# B115X.net
KiCad netlist of a schematic drawn in EAGLE
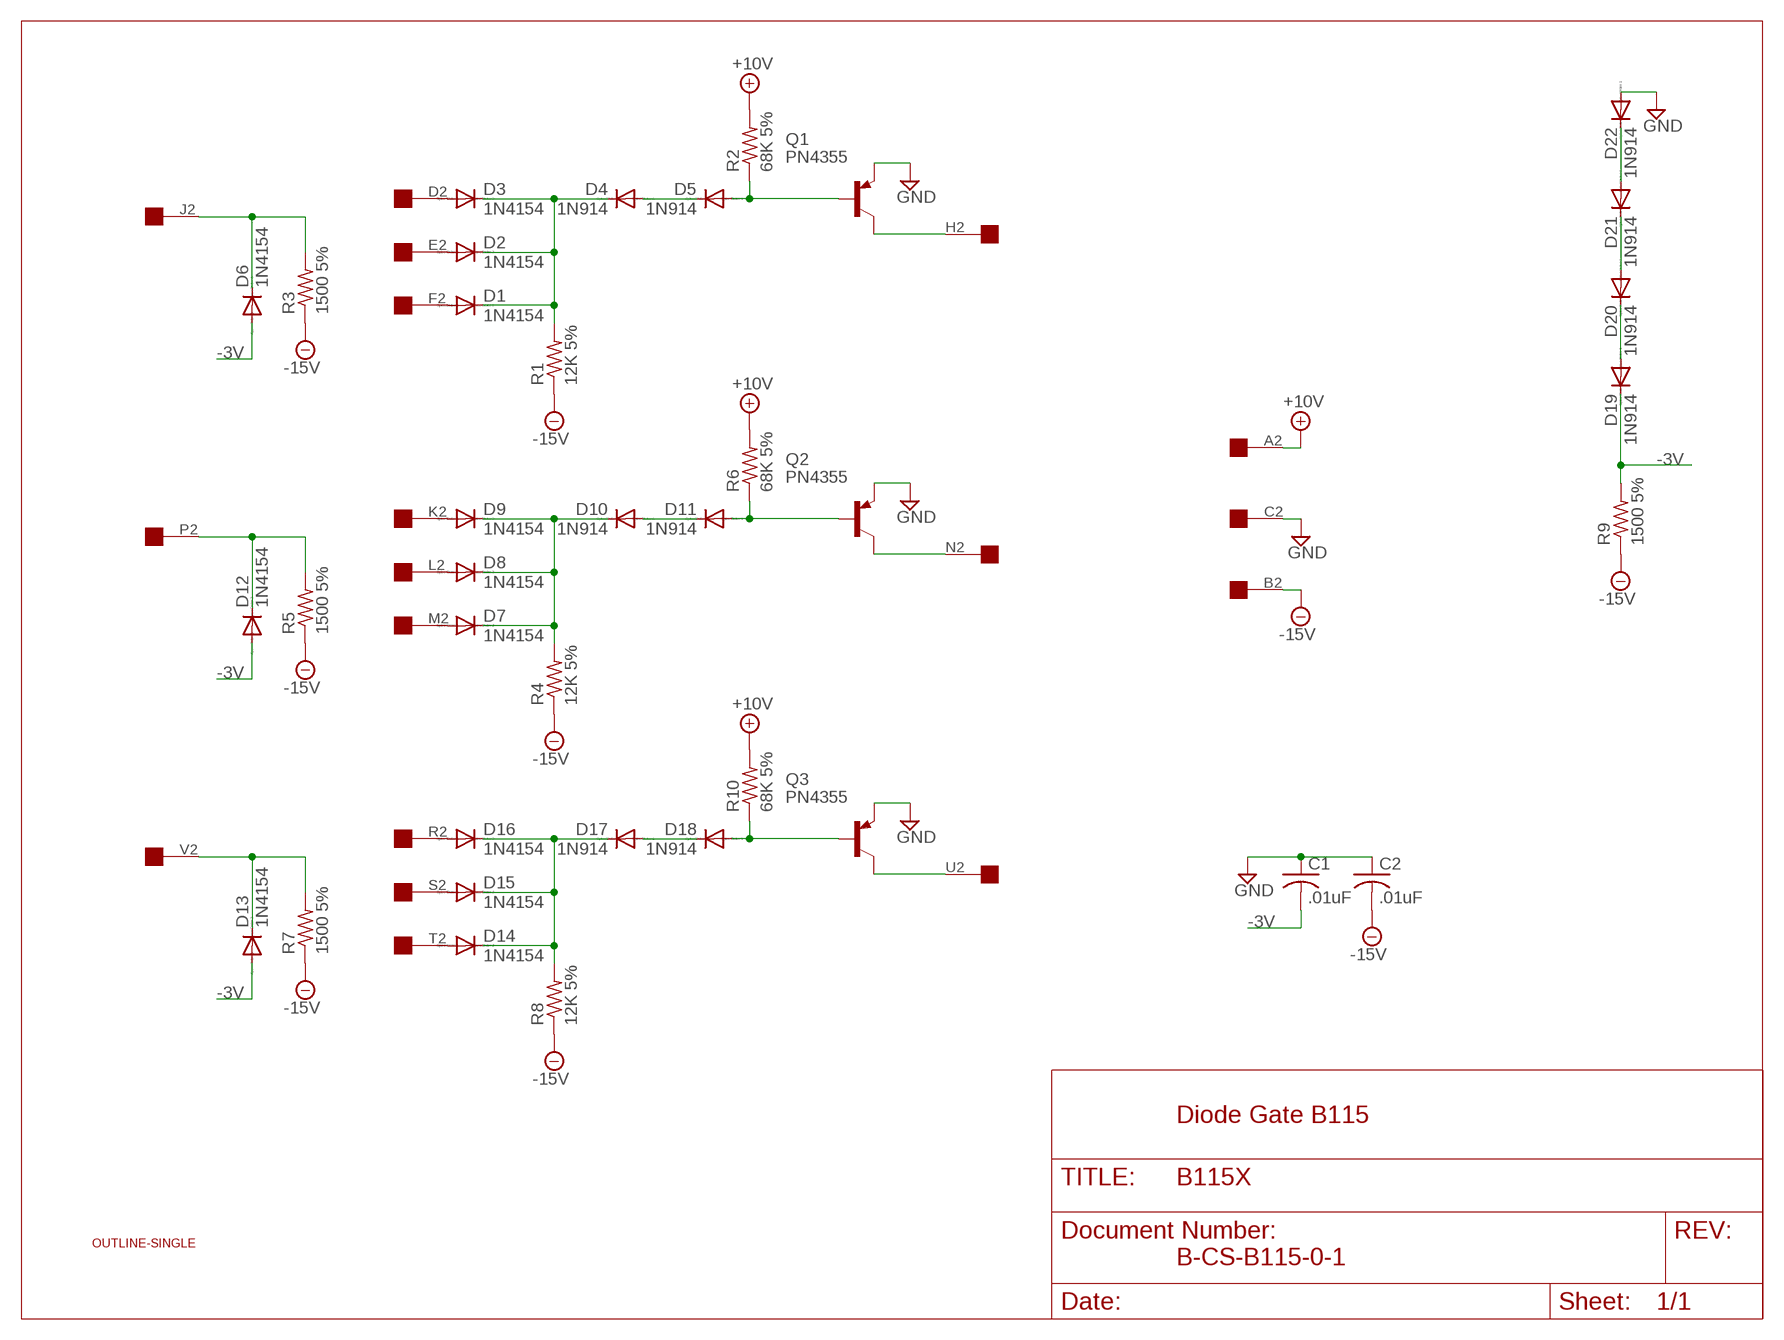
[diagram p0: schematic, sheet 1]

(export (version "E")
  (design (tool "Eeschema 10.0.6"))
  (components
    (comp (ref "C1")
      (value ".01uF")
      (footprint "eagle-import:C050-025X075")
      (libsource (lib "eagle-import") (part "C-US050-025X075"))
    )
    (comp (ref "C2")
      (value ".01uF")
      (footprint "eagle-import:C050-025X075")
      (libsource (lib "eagle-import") (part "C-US050-025X075"))
    )
    (comp (ref "D1")
      (value "1N4154")
      (footprint "eagle-import:DO35-10")
      (libsource (lib "eagle-import") (part "1N4148DO35-10"))
    )
    (comp (ref "D2")
      (value "1N4154")
      (footprint "eagle-import:DO35-10")
      (libsource (lib "eagle-import") (part "1N4148DO35-10"))
    )
    (comp (ref "D3")
      (value "1N4154")
      (footprint "eagle-import:DO35-10")
      (libsource (lib "eagle-import") (part "1N4148DO35-10"))
    )
    (comp (ref "D4")
      (value "1N914")
      (footprint "eagle-import:DO35-10")
      (libsource (lib "eagle-import") (part "1N4148DO35-10"))
    )
    (comp (ref "D5")
      (value "1N914")
      (footprint "eagle-import:DO35-10")
      (libsource (lib "eagle-import") (part "1N4148DO35-10"))
    )
    (comp (ref "D6")
      (value "1N4154")
      (footprint "eagle-import:DO35-10")
      (libsource (lib "eagle-import") (part "1N4148DO35-10"))
    )
    (comp (ref "D7")
      (value "1N4154")
      (footprint "eagle-import:DO35-10")
      (libsource (lib "eagle-import") (part "1N4148DO35-10"))
    )
    (comp (ref "D8")
      (value "1N4154")
      (footprint "eagle-import:DO35-10")
      (libsource (lib "eagle-import") (part "1N4148DO35-10"))
    )
    (comp (ref "D9")
      (value "1N4154")
      (footprint "eagle-import:DO35-10")
      (libsource (lib "eagle-import") (part "1N4148DO35-10"))
    )
    (comp (ref "D10")
      (value "1N914")
      (footprint "eagle-import:DO35-10")
      (libsource (lib "eagle-import") (part "1N4148DO35-10"))
    )
    (comp (ref "D11")
      (value "1N914")
      (footprint "eagle-import:DO35-10")
      (libsource (lib "eagle-import") (part "1N4148DO35-10"))
    )
    (comp (ref "D12")
      (value "1N4154")
      (footprint "eagle-import:DO35-10")
      (libsource (lib "eagle-import") (part "1N4148DO35-10"))
    )
    (comp (ref "D13")
      (value "1N4154")
      (footprint "eagle-import:DO35-10")
      (libsource (lib "eagle-import") (part "1N4148DO35-10"))
    )
    (comp (ref "D14")
      (value "1N4154")
      (footprint "eagle-import:DO35-10")
      (libsource (lib "eagle-import") (part "1N4148DO35-10"))
    )
    (comp (ref "D15")
      (value "1N4154")
      (footprint "eagle-import:DO35-10")
      (libsource (lib "eagle-import") (part "1N4148DO35-10"))
    )
    (comp (ref "D16")
      (value "1N4154")
      (footprint "eagle-import:DO35-10")
      (libsource (lib "eagle-import") (part "1N4148DO35-10"))
    )
    (comp (ref "D17")
      (value "1N914")
      (footprint "eagle-import:DO35-10")
      (libsource (lib "eagle-import") (part "1N4148DO35-10"))
    )
    (comp (ref "D18")
      (value "1N914")
      (footprint "eagle-import:DO35-10")
      (libsource (lib "eagle-import") (part "1N4148DO35-10"))
    )
    (comp (ref "D19")
      (value "1N914")
      (footprint "eagle-import:DO35-10")
      (libsource (lib "eagle-import") (part "1N4148DO35-10"))
    )
    (comp (ref "D20")
      (value "1N914")
      (footprint "eagle-import:DO35-10")
      (libsource (lib "eagle-import") (part "1N4148DO35-10"))
    )
    (comp (ref "D21")
      (value "1N914")
      (footprint "eagle-import:DO35-10")
      (libsource (lib "eagle-import") (part "1N4148DO35-10"))
    )
    (comp (ref "D22")
      (value "1N914")
      (footprint "eagle-import:DO35-10")
      (libsource (lib "eagle-import") (part "1N4148DO35-10"))
    )
    (comp (ref "Q1")
      (value "PN4355")
      (footprint "eagle-import:TO39")
      (libsource (lib "eagle-import") (part "2N2904"))
    )
    (comp (ref "Q2")
      (value "PN4355")
      (footprint "eagle-import:TO39")
      (libsource (lib "eagle-import") (part "2N2904"))
    )
    (comp (ref "Q3")
      (value "PN4355")
      (footprint "eagle-import:TO39")
      (libsource (lib "eagle-import") (part "2N2904"))
    )
    (comp (ref "R1")
      (value "12K 5%")
      (footprint "eagle-import:0207_10")
      (libsource (lib "eagle-import") (part "R-US_0207/10"))
    )
    (comp (ref "R2")
      (value "68K 5%")
      (footprint "eagle-import:0207_10")
      (libsource (lib "eagle-import") (part "R-US_0207/10"))
    )
    (comp (ref "R3")
      (value "1500 5%")
      (footprint "eagle-import:0207_10")
      (libsource (lib "eagle-import") (part "R-US_0207/10"))
    )
    (comp (ref "R4")
      (value "12K 5%")
      (footprint "eagle-import:0207_10")
      (libsource (lib "eagle-import") (part "R-US_0207/10"))
    )
    (comp (ref "R5")
      (value "1500 5%")
      (footprint "eagle-import:0207_10")
      (libsource (lib "eagle-import") (part "R-US_0207/10"))
    )
    (comp (ref "R6")
      (value "68K 5%")
      (footprint "eagle-import:0207_10")
      (libsource (lib "eagle-import") (part "R-US_0207/10"))
    )
    (comp (ref "R7")
      (value "1500 5%")
      (footprint "eagle-import:0207_10")
      (libsource (lib "eagle-import") (part "R-US_0207/10"))
    )
    (comp (ref "R8")
      (value "12K 5%")
      (footprint "eagle-import:0207_10")
      (libsource (lib "eagle-import") (part "R-US_0207/10"))
    )
    (comp (ref "R9")
      (value "1500 5%")
      (footprint "eagle-import:0207_10")
      (libsource (lib "eagle-import") (part "R-US_0207/10"))
    )
    (comp (ref "R10")
      (value "68K 5%")
      (footprint "eagle-import:0207_10")
      (libsource (lib "eagle-import") (part "R-US_0207/10"))
    )
    (comp (ref "U$1")
      (value "OUTLINE-SINGLE")
      (footprint "eagle-import:SINGLE")
      (libsource (lib "eagle-import") (part "OUTLINE-SINGLE"))
    )
    (comp (ref "U$2")
      (value "EDGE-1")
      (footprint "eagle-import:EDGE-CON1")
      (libsource (lib "eagle-import") (part "EDGE-1"))
    )
  )
  (nets
    (net (code "1") (name "+10V") (class "Default")
      (node (ref "R10") (pin "2") (pinfunction "2_2") (pintype "passive"))
      (node (ref "R2") (pin "2") (pinfunction "2_2") (pintype "passive"))
      (node (ref "R6") (pin "2") (pinfunction "2_2") (pintype "passive"))
      (node (ref "U$2") (pin "A2") (pinfunction "1_A2") (pintype "bidirectional"))
    )
    (net (code "2") (name "-15V") (class "Default")
      (node (ref "C2") (pin "2") (pinfunction "2_2") (pintype "passive"))
      (node (ref "R1") (pin "1") (pinfunction "1_1") (pintype "passive"))
      (node (ref "R3") (pin "1") (pinfunction "1_1") (pintype "passive"))
      (node (ref "R4") (pin "1") (pinfunction "1_1") (pintype "passive"))
      (node (ref "R5") (pin "1") (pinfunction "1_1") (pintype "passive"))
      (node (ref "R7") (pin "1") (pinfunction "1_1") (pintype "passive"))
      (node (ref "R8") (pin "1") (pinfunction "1_1") (pintype "passive"))
      (node (ref "R9") (pin "1") (pinfunction "1_1") (pintype "passive"))
      (node (ref "U$2") (pin "B2") (pinfunction "1_B2") (pintype "bidirectional"))
    )
    (net (code "3") (name "/-3V") (class "Default")
      (node (ref "C1") (pin "2") (pinfunction "2_2") (pintype "passive"))
      (node (ref "D12") (pin "A") (pinfunction "A_A") (pintype "passive"))
      (node (ref "D13") (pin "A") (pinfunction "A_A") (pintype "passive"))
      (node (ref "D19") (pin "C") (pinfunction "C_C") (pintype "passive"))
      (node (ref "D6") (pin "A") (pinfunction "A_A") (pintype "passive"))
      (node (ref "R9") (pin "2") (pinfunction "2_2") (pintype "passive"))
    )
    (net (code "4") (name "GND") (class "Default")
      (node (ref "C1") (pin "1") (pinfunction "1_1") (pintype "passive"))
      (node (ref "C2") (pin "1") (pinfunction "1_1") (pintype "passive"))
      (node (ref "D22") (pin "A") (pinfunction "A_A") (pintype "passive"))
      (node (ref "Q1") (pin "1") (pinfunction "E_1") (pintype "passive"))
      (node (ref "Q2") (pin "1") (pinfunction "E_1") (pintype "passive"))
      (node (ref "Q3") (pin "1") (pinfunction "E_1") (pintype "passive"))
      (node (ref "U$2") (pin "C2") (pinfunction "1_C2") (pintype "bidirectional"))
    )
    (net (code "5") (name "Net-(D1-PadC)") (class "Default")
      (node (ref "D1") (pin "C") (pinfunction "C_C") (pintype "passive"))
      (node (ref "D2") (pin "C") (pinfunction "C_C") (pintype "passive"))
      (node (ref "D3") (pin "C") (pinfunction "C_C") (pintype "passive"))
      (node (ref "D4") (pin "C") (pinfunction "C_C") (pintype "passive"))
      (node (ref "R1") (pin "2") (pinfunction "2_2") (pintype "passive"))
    )
    (net (code "6") (name "Net-(D4-PadA)") (class "Default")
      (node (ref "D4") (pin "A") (pinfunction "A_A") (pintype "passive"))
      (node (ref "D5") (pin "C") (pinfunction "C_C") (pintype "passive"))
    )
    (net (code "7") (name "Net-(D10-PadA)") (class "Default")
      (node (ref "D10") (pin "A") (pinfunction "A_A") (pintype "passive"))
      (node (ref "D11") (pin "C") (pinfunction "C_C") (pintype "passive"))
    )
    (net (code "8") (name "Net-(D10-PadC)") (class "Default")
      (node (ref "D10") (pin "C") (pinfunction "C_C") (pintype "passive"))
      (node (ref "D7") (pin "C") (pinfunction "C_C") (pintype "passive"))
      (node (ref "D8") (pin "C") (pinfunction "C_C") (pintype "passive"))
      (node (ref "D9") (pin "C") (pinfunction "C_C") (pintype "passive"))
      (node (ref "R4") (pin "2") (pinfunction "2_2") (pintype "passive"))
    )
    (net (code "9") (name "Net-(D14-PadC)") (class "Default")
      (node (ref "D14") (pin "C") (pinfunction "C_C") (pintype "passive"))
      (node (ref "D15") (pin "C") (pinfunction "C_C") (pintype "passive"))
      (node (ref "D16") (pin "C") (pinfunction "C_C") (pintype "passive"))
      (node (ref "D17") (pin "C") (pinfunction "C_C") (pintype "passive"))
      (node (ref "R8") (pin "2") (pinfunction "2_2") (pintype "passive"))
    )
    (net (code "10") (name "Net-(D17-PadA)") (class "Default")
      (node (ref "D17") (pin "A") (pinfunction "A_A") (pintype "passive"))
      (node (ref "D18") (pin "C") (pinfunction "C_C") (pintype "passive"))
    )
    (net (code "11") (name "Net-(D19-PadA)") (class "Default")
      (node (ref "D19") (pin "A") (pinfunction "A_A") (pintype "passive"))
      (node (ref "D20") (pin "C") (pinfunction "C_C") (pintype "passive"))
    )
    (net (code "12") (name "Net-(D20-PadA)") (class "Default")
      (node (ref "D20") (pin "A") (pinfunction "A_A") (pintype "passive"))
      (node (ref "D21") (pin "C") (pinfunction "C_C") (pintype "passive"))
    )
    (net (code "13") (name "Net-(D21-PadA)") (class "Default")
      (node (ref "D21") (pin "A") (pinfunction "A_A") (pintype "passive"))
      (node (ref "D22") (pin "C") (pinfunction "C_C") (pintype "passive"))
    )
    (net (code "14") (name "Net-(Q1-B)") (class "Default")
      (node (ref "D5") (pin "A") (pinfunction "A_A") (pintype "passive"))
      (node (ref "Q1") (pin "2") (pinfunction "B_2") (pintype "passive"))
      (node (ref "R2") (pin "1") (pinfunction "1_1") (pintype "passive"))
    )
    (net (code "15") (name "Net-(Q1-C)") (class "Default")
      (node (ref "Q1") (pin "3") (pinfunction "C_3") (pintype "passive"))
      (node (ref "U$2") (pin "H2") (pinfunction "1_H2") (pintype "bidirectional"))
    )
    (net (code "16") (name "Net-(Q2-B)") (class "Default")
      (node (ref "D11") (pin "A") (pinfunction "A_A") (pintype "passive"))
      (node (ref "Q2") (pin "2") (pinfunction "B_2") (pintype "passive"))
      (node (ref "R6") (pin "1") (pinfunction "1_1") (pintype "passive"))
    )
    (net (code "17") (name "Net-(Q2-C)") (class "Default")
      (node (ref "Q2") (pin "3") (pinfunction "C_3") (pintype "passive"))
      (node (ref "U$2") (pin "N2") (pinfunction "1_N2") (pintype "bidirectional"))
    )
    (net (code "18") (name "Net-(Q3-B)") (class "Default")
      (node (ref "D18") (pin "A") (pinfunction "A_A") (pintype "passive"))
      (node (ref "Q3") (pin "2") (pinfunction "B_2") (pintype "passive"))
      (node (ref "R10") (pin "1") (pinfunction "1_1") (pintype "passive"))
    )
    (net (code "19") (name "Net-(Q3-C)") (class "Default")
      (node (ref "Q3") (pin "3") (pinfunction "C_3") (pintype "passive"))
      (node (ref "U$2") (pin "U2") (pinfunction "1_U2") (pintype "bidirectional"))
    )
    (net (code "20") (name "Net-(U$2D-1)") (class "Default")
      (node (ref "D3") (pin "A") (pinfunction "A_A") (pintype "passive"))
      (node (ref "U$2") (pin "D2") (pinfunction "1_D2") (pintype "bidirectional"))
    )
    (net (code "21") (name "Net-(U$2E-1)") (class "Default")
      (node (ref "D2") (pin "A") (pinfunction "A_A") (pintype "passive"))
      (node (ref "U$2") (pin "E2") (pinfunction "1_E2") (pintype "bidirectional"))
    )
    (net (code "22") (name "Net-(U$2F-1)") (class "Default")
      (node (ref "D1") (pin "A") (pinfunction "A_A") (pintype "passive"))
      (node (ref "U$2") (pin "F2") (pinfunction "1_F2") (pintype "bidirectional"))
    )
    (net (code "23") (name "Net-(U$2H-1)") (class "Default")
      (node (ref "D6") (pin "C") (pinfunction "C_C") (pintype "passive"))
      (node (ref "R3") (pin "2") (pinfunction "2_2") (pintype "passive"))
      (node (ref "U$2") (pin "J2") (pinfunction "1_J2") (pintype "bidirectional"))
    )
    (net (code "24") (name "Net-(U$2I-1)") (class "Default")
      (node (ref "D9") (pin "A") (pinfunction "A_A") (pintype "passive"))
      (node (ref "U$2") (pin "K2") (pinfunction "1_K2") (pintype "bidirectional"))
    )
    (net (code "25") (name "Net-(U$2J-1)") (class "Default")
      (node (ref "D8") (pin "A") (pinfunction "A_A") (pintype "passive"))
      (node (ref "U$2") (pin "L2") (pinfunction "1_L2") (pintype "bidirectional"))
    )
    (net (code "26") (name "Net-(U$2K-1)") (class "Default")
      (node (ref "D7") (pin "A") (pinfunction "A_A") (pintype "passive"))
      (node (ref "U$2") (pin "M2") (pinfunction "1_M2") (pintype "bidirectional"))
    )
    (net (code "27") (name "Net-(U$2M-1)") (class "Default")
      (node (ref "D12") (pin "C") (pinfunction "C_C") (pintype "passive"))
      (node (ref "R5") (pin "2") (pinfunction "2_2") (pintype "passive"))
      (node (ref "U$2") (pin "P2") (pinfunction "1_P2") (pintype "bidirectional"))
    )
    (net (code "28") (name "Net-(U$2N-1)") (class "Default")
      (node (ref "D16") (pin "A") (pinfunction "A_A") (pintype "passive"))
      (node (ref "U$2") (pin "R2") (pinfunction "1_R2") (pintype "bidirectional"))
    )
    (net (code "29") (name "Net-(U$2O-1)") (class "Default")
      (node (ref "D15") (pin "A") (pinfunction "A_A") (pintype "passive"))
      (node (ref "U$2") (pin "S2") (pinfunction "1_S2") (pintype "bidirectional"))
    )
    (net (code "30") (name "Net-(U$2P-1)") (class "Default")
      (node (ref "D14") (pin "A") (pinfunction "A_A") (pintype "passive"))
      (node (ref "U$2") (pin "T2") (pinfunction "1_T2") (pintype "bidirectional"))
    )
    (net (code "31") (name "Net-(U$2R-1)") (class "Default")
      (node (ref "D13") (pin "C") (pinfunction "C_C") (pintype "passive"))
      (node (ref "R7") (pin "2") (pinfunction "2_2") (pintype "passive"))
      (node (ref "U$2") (pin "V2") (pinfunction "1_V2") (pintype "bidirectional"))
    )
  )
)
